# MYBOARD_05-PWR.net
KiCad netlist of a schematic drawn in Altium Designer
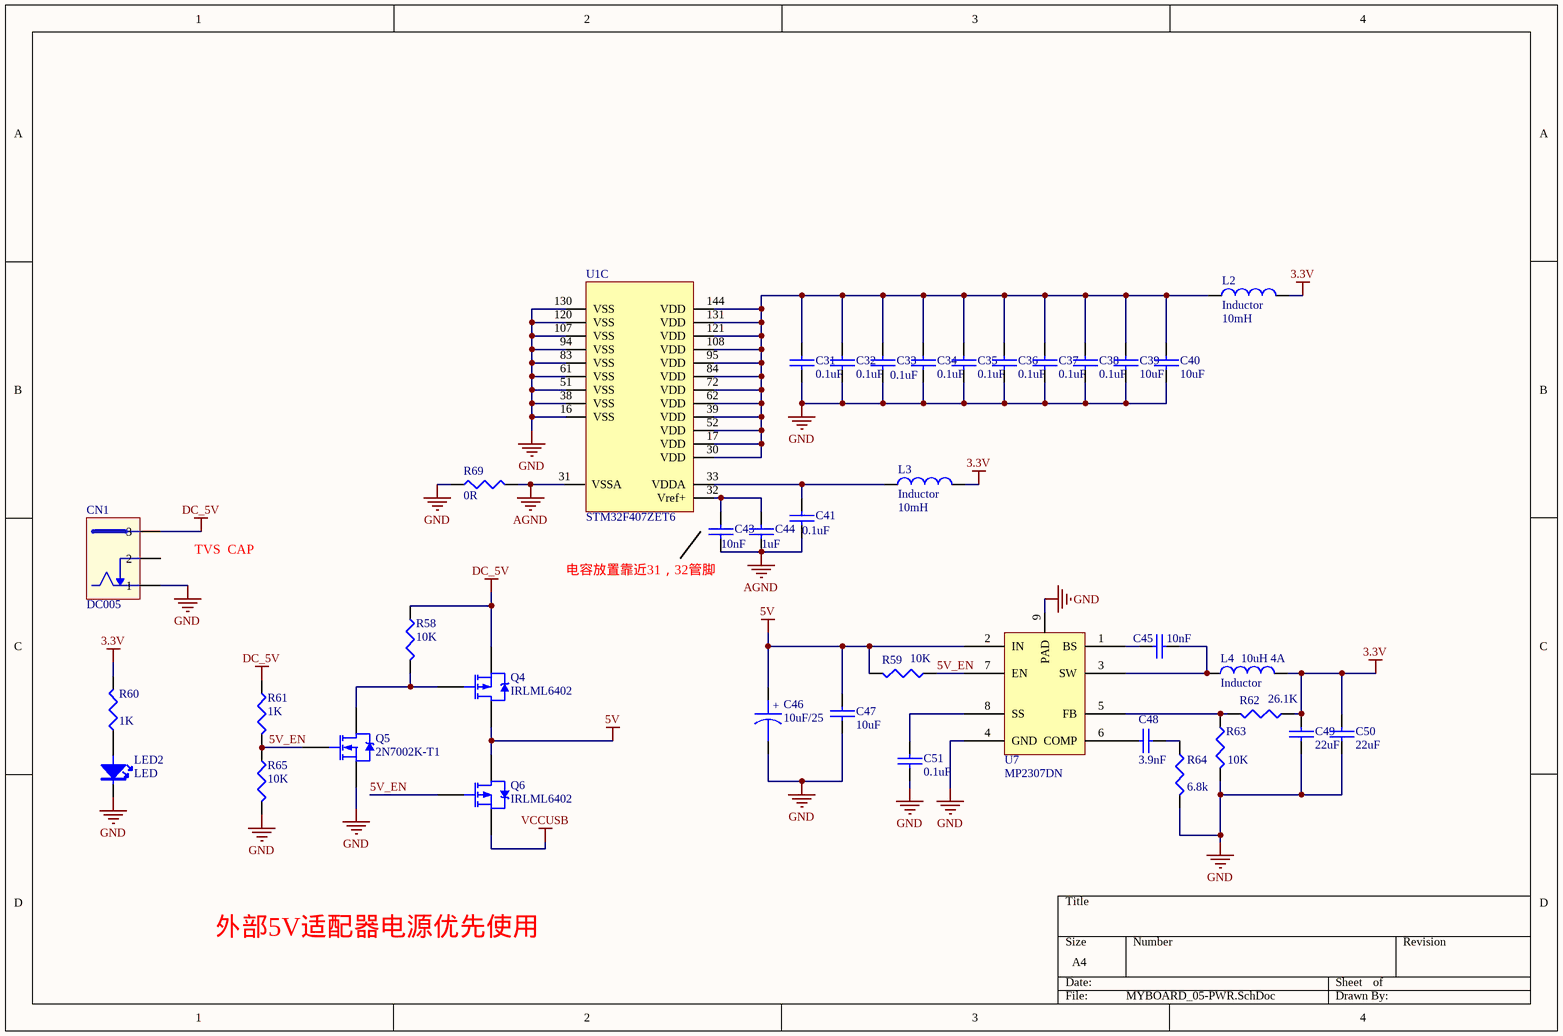
[diagram p0: MYBOARD_05-PWR.SchDoc]

(export (version "E")
  (design (tool "Eeschema 10.0.6"))
  (components
    (comp (ref "C31")
      (value "0.1uF")
      (footprint "C0603_DWS")
      (description "Capacitor")
      (libsource (lib "ortho fixture") (part "CAP"))
    )
    (comp (ref "C32")
      (value "0.1uF")
      (footprint "C0603_DWS")
      (description "Capacitor")
      (libsource (lib "ortho fixture") (part "CAP"))
    )
    (comp (ref "C33")
      (value "0.1uF")
      (footprint "C0603_DWS")
      (description "Capacitor")
      (libsource (lib "ortho fixture") (part "CAP"))
    )
    (comp (ref "C34")
      (value "0.1uF")
      (footprint "C0603_DWS")
      (description "Capacitor")
      (libsource (lib "ortho fixture") (part "CAP"))
    )
    (comp (ref "C35")
      (value "0.1uF")
      (footprint "C0603_DWS")
      (description "Capacitor")
      (libsource (lib "ortho fixture") (part "CAP"))
    )
    (comp (ref "C36")
      (value "0.1uF")
      (footprint "C0603_DWS")
      (description "Capacitor")
      (libsource (lib "ortho fixture") (part "CAP"))
    )
    (comp (ref "C37")
      (value "0.1uF")
      (footprint "C0603_DWS")
      (description "Capacitor")
      (libsource (lib "ortho fixture") (part "CAP"))
    )
    (comp (ref "C38")
      (value "0.1uF")
      (footprint "C0603_DWS")
      (description "Capacitor")
      (libsource (lib "ortho fixture") (part "CAP"))
    )
    (comp (ref "C39")
      (value "10uF")
      (footprint "C0603_DWS")
      (description "Capacitor")
      (libsource (lib "ortho fixture") (part "CAP"))
    )
    (comp (ref "C40")
      (value "10uF")
      (footprint "C0603_DWS")
      (description "Capacitor")
      (libsource (lib "ortho fixture") (part "CAP"))
    )
    (comp (ref "C41")
      (value "0.1uF")
      (footprint "C0603_DWS")
      (description "Capacitor")
      (libsource (lib "ortho fixture") (part "CAP"))
    )
    (comp (ref "C43")
      (value "10nF")
      (footprint "C0603_DWS")
      (description "Capacitor")
      (libsource (lib "ortho fixture") (part "CAP"))
    )
    (comp (ref "C44")
      (value "1uF")
      (footprint "C0603_DWS")
      (description "Capacitor")
      (libsource (lib "ortho fixture") (part "CAP"))
    )
    (comp (ref "C45")
      (value "10nF")
      (footprint "C0603_DWS")
      (description "Capacitor")
      (libsource (lib "ortho fixture") (part "CAP"))
    )
    (comp (ref "C46")
      (value "10uF/25")
      (footprint "CAPAE7053X56M")
      (description "Aluminum Electrolytic Capacitor SMD  Footprint:SizeCode_C")
      (fields
        (field (name "MANUFACTURER") "Panasonic")
        (field (name "MANUFACTURER PART NUMBER") "EEE1EA100SR")
      )
      (libsource (lib "ortho fixture") (part "EEE1EA100SR"))
    )
    (comp (ref "C47")
      (value "10uF")
      (footprint "C1206")
      (description "Capacitor")
      (libsource (lib "ortho fixture") (part "CAP"))
    )
    (comp (ref "C48")
      (value "3.9nF")
      (footprint "C0603_DWS")
      (description "Capacitor")
      (libsource (lib "ortho fixture") (part "CAP"))
    )
    (comp (ref "C49")
      (value "22uF")
      (footprint "C1206")
      (description "Capacitor")
      (libsource (lib "ortho fixture") (part "CAP"))
    )
    (comp (ref "C50")
      (value "22uF")
      (footprint "C1206")
      (description "Capacitor")
      (libsource (lib "ortho fixture") (part "CAP"))
    )
    (comp (ref "C51")
      (value "0.1uF")
      (footprint "C0603_DWS")
      (description "Capacitor")
      (libsource (lib "ortho fixture") (part "CAP"))
    )
    (comp (ref "CN1")
      (value "DC005")
      (footprint "PWR_JACK_UNI_MILLING")
      (description "3pin, 5mm, DC input connect,")
      (libsource (lib "ortho fixture") (part "DC005"))
    )
    (comp (ref "L2")
      (value "Inductor")
      (footprint "0603")
      (fields (field (name "ALTIUM_VALUE") "10mH") (field (name "PUBLISHER") "Altium Limited"))
      (libsource (lib "Miscellaneous Devices") (part "Inductor"))
    )
    (comp (ref "L3")
      (value "Inductor")
      (footprint "0603")
      (fields (field (name "ALTIUM_VALUE") "10mH") (field (name "PUBLISHER") "Altium Limited"))
      (libsource (lib "Miscellaneous Devices") (part "Inductor"))
    )
    (comp (ref "L4")
      (value "Inductor")
      (footprint "CD32")
      (fields (field (name "ALTIUM_VALUE") "10uH 4A") (field (name "PUBLISHER") "Altium Limited"))
      (libsource (lib "Miscellaneous Devices") (part "Inductor"))
    )
    (comp (ref "LED2") (value "LED") (footprint "LED-0603") (libsource (lib "ortho fixture") (part "LED")))
    (comp (ref "Q4")
      (value "IRLML6402")
      (footprint "SOTFL95P264X112-3N")
      (description "HEXFET Power MOSFET")
      (fields (field (name "PUBLISHER") "Altium Limited"))
      (libsource (lib "IR Discrete MOSFET - Power") (part "IRLML6401"))
    )
    (comp (ref "Q5")
      (value "2N7002K-T1")
      (footprint "SOT23")
      (description "N-MOS SOT-23")
      (libsource (lib "ortho fixture") (part "2N7002K-T1"))
    )
    (comp (ref "Q6")
      (value "IRLML6402")
      (footprint "SOTFL95P264X112-3N")
      (description "HEXFET Power MOSFET")
      (fields (field (name "PUBLISHER") "Altium Limited"))
      (libsource (lib "IR Discrete MOSFET - Power") (part "IRLML6401"))
    )
    (comp (ref "R58")
      (value "10K")
      (footprint "R0603_5MIL_DWS")
      (description "Resistor")
      (fields (field (name "Comment") "Res3") (field (name "PUBLISHER") "Altium Limited"))
      (libsource (lib "Miscellaneous Devices") (part "Res3"))
    )
    (comp (ref "R59")
      (value "10K")
      (footprint "R0603_5MIL_DWS")
      (description "Resistor")
      (fields (field (name "Comment") "Res3") (field (name "PUBLISHER") "Altium Limited"))
      (libsource (lib "Miscellaneous Devices") (part "Res3"))
    )
    (comp (ref "R60")
      (value "1K")
      (footprint "R0603_5MIL_DWS")
      (description "Resistor")
      (fields (field (name "Comment") "Res3") (field (name "PUBLISHER") "Altium Limited"))
      (libsource (lib "Miscellaneous Devices") (part "Res3"))
    )
    (comp (ref "R61")
      (value "1K")
      (footprint "R0603_5MIL_DWS")
      (description "Resistor")
      (fields (field (name "Comment") "Res3") (field (name "PUBLISHER") "Altium Limited"))
      (libsource (lib "Miscellaneous Devices") (part "Res3"))
    )
    (comp (ref "R62")
      (value "26.1K")
      (footprint "R0603_5MIL_DWS")
      (description "Resistor")
      (fields (field (name "Comment") "Res3") (field (name "PUBLISHER") "Altium Limited"))
      (libsource (lib "Miscellaneous Devices") (part "Res3"))
    )
    (comp (ref "R63")
      (value "10K")
      (footprint "R0603_5MIL_DWS")
      (description "Resistor")
      (fields (field (name "Comment") "Res3") (field (name "PUBLISHER") "Altium Limited"))
      (libsource (lib "Miscellaneous Devices") (part "Res3"))
    )
    (comp (ref "R64")
      (value "6.8k")
      (footprint "R0603_5MIL_DWS")
      (description "Resistor")
      (fields (field (name "Comment") "Res3") (field (name "PUBLISHER") "Altium Limited"))
      (libsource (lib "Miscellaneous Devices") (part "Res3"))
    )
    (comp (ref "R65")
      (value "10K")
      (footprint "R0603_5MIL_DWS")
      (description "Resistor")
      (fields (field (name "Comment") "Res3") (field (name "PUBLISHER") "Altium Limited"))
      (libsource (lib "Miscellaneous Devices") (part "Res3"))
    )
    (comp (ref "R69")
      (value "0R")
      (footprint "R0603_5MIL_DWS")
      (description "Resistor")
      (fields (field (name "Comment") "Res3") (field (name "PUBLISHER") "Altium Limited"))
      (libsource (lib "Miscellaneous Devices") (part "Res3"))
    )
    (comp (ref "U1")
      (value "STM32F407ZET6")
      (footprint "LQFP144")
      (libsource (lib "ortho fixture") (part "STM32F407ZET6"))
    )
    (comp (ref "U7")
      (value "MP2307DN")
      (footprint "SOIC-8")
      (description "DC-DC  4.75-23V INPUT SOIC-8  3A")
      (libsource (lib "ortho fixture") (part "MP2307DN"))
    )
  )
  (nets
    (net (code "1") (name "/5V_EN") (class "Default")
      (node (ref "Q5") (pin "1") (pinfunction "G_1") (pintype "passive"))
      (node (ref "Q6") (pin "1") (pinfunction "G_1") (pintype "passive"))
      (node (ref "R59") (pin "1") (pinfunction "1_1") (pintype "passive"))
      (node (ref "R61") (pin "2") (pinfunction "2_2") (pintype "passive"))
      (node (ref "R65") (pin "1") (pinfunction "1_1") (pintype "passive"))
      (node (ref "U7") (pin "7") (pinfunction "EN_7") (pintype "power_in"))
    )
    (net (code "2") (name "3.3V") (class "Default")
      (node (ref "C49") (pin "1") (pinfunction "1_1") (pintype "passive"))
      (node (ref "C50") (pin "1") (pinfunction "1_1") (pintype "passive"))
      (node (ref "L2") (pin "2") (pinfunction "2_2") (pintype "passive"))
      (node (ref "L3") (pin "2") (pinfunction "2_2") (pintype "passive"))
      (node (ref "L4") (pin "2") (pinfunction "2_2") (pintype "passive"))
      (node (ref "R60") (pin "2") (pinfunction "2_2") (pintype "passive"))
      (node (ref "R62") (pin "1") (pinfunction "1_1") (pintype "passive"))
    )
    (net (code "3") (name "5V") (class "Default")
      (node (ref "C46") (pin "1") (pinfunction "1_1") (pintype "passive"))
      (node (ref "C47") (pin "1") (pinfunction "1_1") (pintype "passive"))
      (node (ref "Q4") (pin "3") (pinfunction "D_3") (pintype "passive"))
      (node (ref "Q6") (pin "3") (pinfunction "D_3") (pintype "passive"))
      (node (ref "R59") (pin "2") (pinfunction "2_2") (pintype "passive"))
      (node (ref "U7") (pin "2") (pinfunction "IN_2") (pintype "power_in"))
    )
    (net (code "4") (name "AGND") (class "Default")
      (node (ref "C41") (pin "2") (pinfunction "2_2") (pintype "passive"))
      (node (ref "C43") (pin "2") (pinfunction "2_2") (pintype "passive"))
      (node (ref "C44") (pin "2") (pinfunction "2_2") (pintype "passive"))
      (node (ref "R69") (pin "2") (pinfunction "2_2") (pintype "passive"))
      (node (ref "U1") (pin "31") (pinfunction "VSSA_31") (pintype "passive"))
    )
    (net (code "5") (name "DC_5V") (class "Default")
      (node (ref "CN1") (pin "+") (pinfunction "3_+") (pintype "passive"))
      (node (ref "Q4") (pin "2") (pinfunction "S_2") (pintype "passive"))
      (node (ref "R58") (pin "1") (pinfunction "1_1") (pintype "passive"))
      (node (ref "R61") (pin "1") (pinfunction "1_1") (pintype "passive"))
    )
    (net (code "6") (name "GND") (class "Default")
      (node (ref "C31") (pin "2") (pinfunction "2_2") (pintype "passive"))
      (node (ref "C32") (pin "2") (pinfunction "2_2") (pintype "passive"))
      (node (ref "C33") (pin "2") (pinfunction "2_2") (pintype "passive"))
      (node (ref "C34") (pin "2") (pinfunction "2_2") (pintype "passive"))
      (node (ref "C35") (pin "2") (pinfunction "2_2") (pintype "passive"))
      (node (ref "C36") (pin "2") (pinfunction "2_2") (pintype "passive"))
      (node (ref "C37") (pin "2") (pinfunction "2_2") (pintype "passive"))
      (node (ref "C38") (pin "2") (pinfunction "2_2") (pintype "passive"))
      (node (ref "C39") (pin "2") (pinfunction "2_2") (pintype "passive"))
      (node (ref "C40") (pin "2") (pinfunction "2_2") (pintype "passive"))
      (node (ref "C46") (pin "2") (pinfunction "2_2") (pintype "passive"))
      (node (ref "C47") (pin "2") (pinfunction "2_2") (pintype "passive"))
      (node (ref "C49") (pin "2") (pinfunction "2_2") (pintype "passive"))
      (node (ref "C50") (pin "2") (pinfunction "2_2") (pintype "passive"))
      (node (ref "C51") (pin "2") (pinfunction "2_2") (pintype "passive"))
      (node (ref "CN1") (pin "--") (pinfunction "1_--") (pintype "passive"))
      (node (ref "LED2") (pin "C") (pinfunction "C_C") (pintype "passive"))
      (node (ref "Q5") (pin "2") (pinfunction "S_2") (pintype "passive"))
      (node (ref "R63") (pin "2") (pinfunction "2_2") (pintype "passive"))
      (node (ref "R64") (pin "2") (pinfunction "2_2") (pintype "passive"))
      (node (ref "R65") (pin "2") (pinfunction "2_2") (pintype "passive"))
      (node (ref "R69") (pin "1") (pinfunction "1_1") (pintype "passive"))
      (node (ref "U1") (pin "107") (pinfunction "VSS_107") (pintype "passive"))
      (node (ref "U1") (pin "120") (pinfunction "VSS_120") (pintype "passive"))
      (node (ref "U1") (pin "130") (pinfunction "VSS_130") (pintype "passive"))
      (node (ref "U1") (pin "16") (pinfunction "VSS_16") (pintype "passive"))
      (node (ref "U1") (pin "38") (pinfunction "VSS_38") (pintype "passive"))
      (node (ref "U1") (pin "51") (pinfunction "VSS_51") (pintype "passive"))
      (node (ref "U1") (pin "61") (pinfunction "VSS_61") (pintype "passive"))
      (node (ref "U1") (pin "83") (pinfunction "VSS_83") (pintype "passive"))
      (node (ref "U1") (pin "94") (pinfunction "VSS_94") (pintype "passive"))
      (node (ref "U7") (pin "4") (pinfunction "GND_4") (pintype "power_in"))
      (node (ref "U7") (pin "9") (pinfunction "PAD_9") (pintype "passive"))
    )
    (net (code "7") (name "Net-(C31-Pad1)") (class "Default")
      (node (ref "C31") (pin "1") (pinfunction "1_1") (pintype "passive"))
      (node (ref "C32") (pin "1") (pinfunction "1_1") (pintype "passive"))
      (node (ref "C33") (pin "1") (pinfunction "1_1") (pintype "passive"))
      (node (ref "C34") (pin "1") (pinfunction "1_1") (pintype "passive"))
      (node (ref "C35") (pin "1") (pinfunction "1_1") (pintype "passive"))
      (node (ref "C36") (pin "1") (pinfunction "1_1") (pintype "passive"))
      (node (ref "C37") (pin "1") (pinfunction "1_1") (pintype "passive"))
      (node (ref "C38") (pin "1") (pinfunction "1_1") (pintype "passive"))
      (node (ref "C39") (pin "1") (pinfunction "1_1") (pintype "passive"))
      (node (ref "C40") (pin "1") (pinfunction "1_1") (pintype "passive"))
      (node (ref "L2") (pin "1") (pinfunction "1_1") (pintype "passive"))
      (node (ref "U1") (pin "108") (pinfunction "VDD_108") (pintype "passive"))
      (node (ref "U1") (pin "121") (pinfunction "VDD_121") (pintype "passive"))
      (node (ref "U1") (pin "131") (pinfunction "VDD_131") (pintype "passive"))
      (node (ref "U1") (pin "144") (pinfunction "VDD_144") (pintype "passive"))
      (node (ref "U1") (pin "17") (pinfunction "VDD_17") (pintype "passive"))
      (node (ref "U1") (pin "30") (pinfunction "VDD_30") (pintype "passive"))
      (node (ref "U1") (pin "39") (pinfunction "VDD_39") (pintype "passive"))
      (node (ref "U1") (pin "52") (pinfunction "VDD_52") (pintype "passive"))
      (node (ref "U1") (pin "62") (pinfunction "VDD_62") (pintype "passive"))
      (node (ref "U1") (pin "72") (pinfunction "VDD_72") (pintype "passive"))
      (node (ref "U1") (pin "84") (pinfunction "VDD_84") (pintype "passive"))
      (node (ref "U1") (pin "95") (pinfunction "VDD_95") (pintype "passive"))
    )
    (net (code "8") (name "Net-(C48-Pad2)") (class "Default")
      (node (ref "C48") (pin "2") (pinfunction "2_2") (pintype "passive"))
      (node (ref "R64") (pin "1") (pinfunction "1_1") (pintype "passive"))
    )
    (net (code "9") (name "Net-(LED2-1)") (class "Default")
      (node (ref "LED2") (pin "A") (pinfunction "1_A") (pintype "passive"))
      (node (ref "R60") (pin "1") (pinfunction "1_1") (pintype "passive"))
    )
    (net (code "10") (name "Net-(Q4-G)") (class "Default")
      (node (ref "Q4") (pin "1") (pinfunction "G_1") (pintype "passive"))
      (node (ref "Q5") (pin "3") (pinfunction "D_3") (pintype "passive"))
      (node (ref "R58") (pin "2") (pinfunction "2_2") (pintype "passive"))
    )
    (net (code "11") (name "Net-(U1C-VDDA)") (class "Default")
      (node (ref "C41") (pin "1") (pinfunction "1_1") (pintype "passive"))
      (node (ref "L3") (pin "1") (pinfunction "1_1") (pintype "passive"))
      (node (ref "U1") (pin "33") (pinfunction "VDDA_33") (pintype "passive"))
    )
    (net (code "12") (name "Net-(U1C-Vref+)") (class "Default")
      (node (ref "C43") (pin "1") (pinfunction "1_1") (pintype "passive"))
      (node (ref "C44") (pin "1") (pinfunction "1_1") (pintype "passive"))
      (node (ref "U1") (pin "32") (pinfunction "Vref+_32") (pintype "passive"))
    )
    (net (code "13") (name "Net-(U7-BS)") (class "Default")
      (node (ref "C45") (pin "1") (pinfunction "1_1") (pintype "passive"))
      (node (ref "U7") (pin "1") (pinfunction "BS_1") (pintype "power_in"))
    )
    (net (code "14") (name "Net-(U7-COMP)") (class "Default")
      (node (ref "C48") (pin "1") (pinfunction "1_1") (pintype "passive"))
      (node (ref "U7") (pin "6") (pinfunction "COMP_6") (pintype "power_in"))
    )
    (net (code "15") (name "Net-(U7-FB)") (class "Default")
      (node (ref "R62") (pin "2") (pinfunction "2_2") (pintype "passive"))
      (node (ref "R63") (pin "1") (pinfunction "1_1") (pintype "passive"))
      (node (ref "U7") (pin "5") (pinfunction "FB_5") (pintype "power_in"))
    )
    (net (code "16") (name "Net-(U7-SS)") (class "Default")
      (node (ref "C51") (pin "1") (pinfunction "1_1") (pintype "passive"))
      (node (ref "U7") (pin "8") (pinfunction "SS_8") (pintype "power_in"))
    )
    (net (code "17") (name "Net-(U7-SW)") (class "Default")
      (node (ref "C45") (pin "2") (pinfunction "2_2") (pintype "passive"))
      (node (ref "L4") (pin "1") (pinfunction "1_1") (pintype "passive"))
      (node (ref "U7") (pin "3") (pinfunction "SW_3") (pintype "power_in"))
    )
    (net (code "18") (name "VCCUSB") (class "Default")
      (node (ref "Q6") (pin "2") (pinfunction "S_2") (pintype "passive"))
    )
    (net (code "19") (name "unconnected-(CN1-2-Pad-)") (class "Default")
      (node (ref "CN1") (pin "-") (pinfunction "2_-") (pintype "passive"))
    )
  )
)
